# SD_agronautes.net
KiCad netlist of a schematic drawn in EAGLE
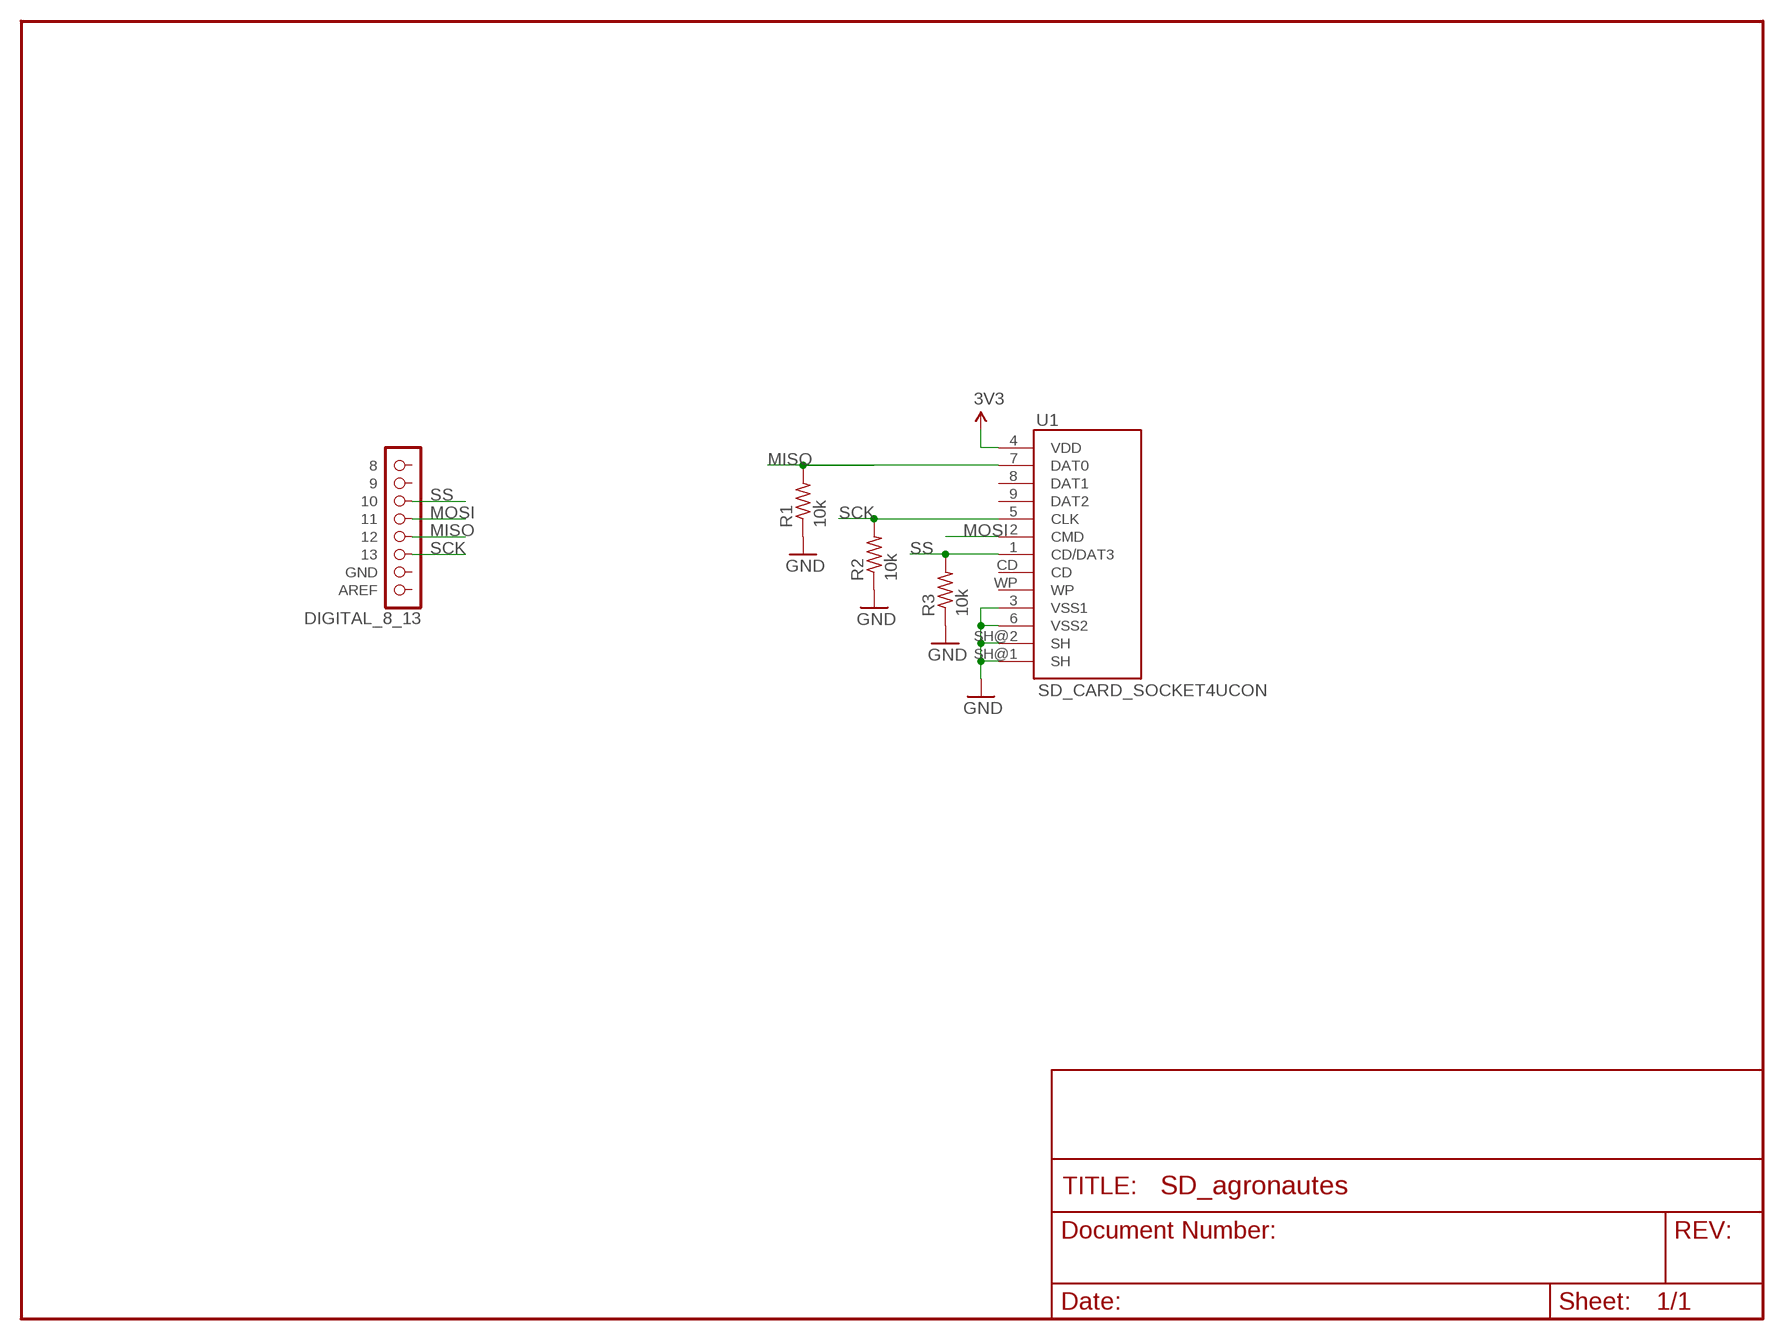
[diagram p0: schematic, sheet 1]

(export (version "E")
  (design (tool "Eeschema 10.0.6"))
  (components
    (comp (ref "R1")
      (value "10k")
      (footprint "eagle-import:0207_10")
      (libsource (lib "eagle-import") (part "R-US_0207/10"))
    )
    (comp (ref "R2")
      (value "10k")
      (footprint "eagle-import:0207_10")
      (libsource (lib "eagle-import") (part "R-US_0207/10"))
    )
    (comp (ref "R3")
      (value "10k")
      (footprint "eagle-import:0207_10")
      (libsource (lib "eagle-import") (part "R-US_0207/10"))
    )
    (comp (ref "U$2")
      (value "DIGITAL_8_13")
      (footprint "eagle-import:1X08")
      (libsource (lib "eagle-import") (part "DIGITAL_8_13"))
    )
    (comp (ref "U1")
      (value "SD_CARD_SOCKET4UCON")
      (footprint "eagle-import:SDCARD_4UCONN")
      (libsource (lib "eagle-import") (part "SD_CARD_SOCKET4UCON"))
    )
  )
  (nets
    (net (code "1") (name "/MISO") (class "Default")
      (node (ref "R1") (pin "2") (pinfunction "2_2") (pintype "passive"))
      (node (ref "U$2") (pin "4") (pinfunction "12_4") (pintype "passive"))
      (node (ref "U1") (pin "7") (pinfunction "DAT0_7") (pintype "bidirectional"))
    )
    (net (code "2") (name "/MOSI") (class "Default")
      (node (ref "U$2") (pin "5") (pinfunction "11_5") (pintype "passive"))
      (node (ref "U1") (pin "2") (pinfunction "CMD_2") (pintype "bidirectional"))
    )
    (net (code "3") (name "/SCK") (class "Default")
      (node (ref "R2") (pin "2") (pinfunction "2_2") (pintype "passive"))
      (node (ref "U$2") (pin "3") (pinfunction "13_3") (pintype "passive"))
      (node (ref "U1") (pin "5") (pinfunction "CLK_5") (pintype "bidirectional"))
    )
    (net (code "4") (name "/SS") (class "Default")
      (node (ref "R3") (pin "2") (pinfunction "2_2") (pintype "passive"))
      (node (ref "U$2") (pin "6") (pinfunction "10_6") (pintype "passive"))
      (node (ref "U1") (pin "1") (pinfunction "CD/DAT3_1") (pintype "bidirectional"))
    )
    (net (code "5") (name "3V3") (class "Default")
      (node (ref "U1") (pin "4") (pinfunction "VDD_4") (pintype "power_in"))
    )
    (net (code "6") (name "GND") (class "Default")
      (node (ref "R1") (pin "1") (pinfunction "1_1") (pintype "passive"))
      (node (ref "R2") (pin "1") (pinfunction "1_1") (pintype "passive"))
      (node (ref "R3") (pin "1") (pinfunction "1_1") (pintype "passive"))
      (node (ref "U1") (pin "3") (pinfunction "VSS1_3") (pintype "power_in"))
      (node (ref "U1") (pin "6") (pinfunction "VSS2_6") (pintype "power_in"))
      (node (ref "U1") (pin "SH@1") (pinfunction "SH_SH@1") (pintype "bidirectional"))
      (node (ref "U1") (pin "SH@2") (pinfunction "SH_SH@2") (pintype "bidirectional"))
    )
    (net (code "7") (name "unconnected-(U$2-9-Pad7)") (class "Default")
      (node (ref "U$2") (pin "7") (pinfunction "9_7") (pintype "passive"))
    )
    (net (code "8") (name "unconnected-(U$2-AREF-Pad1)") (class "Default")
      (node (ref "U$2") (pin "1") (pinfunction "AREF_1") (pintype "passive"))
    )
    (net (code "9") (name "unconnected-(U$2-GND-Pad2)") (class "Default")
      (node (ref "U$2") (pin "2") (pinfunction "GND_2") (pintype "passive"))
    )
    (net (code "10") (name "unconnected-(U$2-Pad8)") (class "Default")
      (node (ref "U$2") (pin "8") (pinfunction "8_8") (pintype "passive"))
    )
    (net (code "11") (name "unconnected-(U1-DAT1-Pad8)") (class "Default")
      (node (ref "U1") (pin "8") (pinfunction "DAT1_8") (pintype "bidirectional"))
    )
    (net (code "12") (name "unconnected-(U1-DAT2-Pad9)") (class "Default")
      (node (ref "U1") (pin "9") (pinfunction "DAT2_9") (pintype "bidirectional"))
    )
    (net (code "13") (name "unconnected-(U1-PadCD)") (class "Default")
      (node (ref "U1") (pin "CD") (pinfunction "CD_CD") (pintype "bidirectional"))
    )
    (net (code "14") (name "unconnected-(U1-PadWP)") (class "Default")
      (node (ref "U1") (pin "WP") (pinfunction "WP_WP") (pintype "bidirectional"))
    )
  )
)
